# Sheet1.net
KiCad netlist of a schematic drawn in Altium Designer
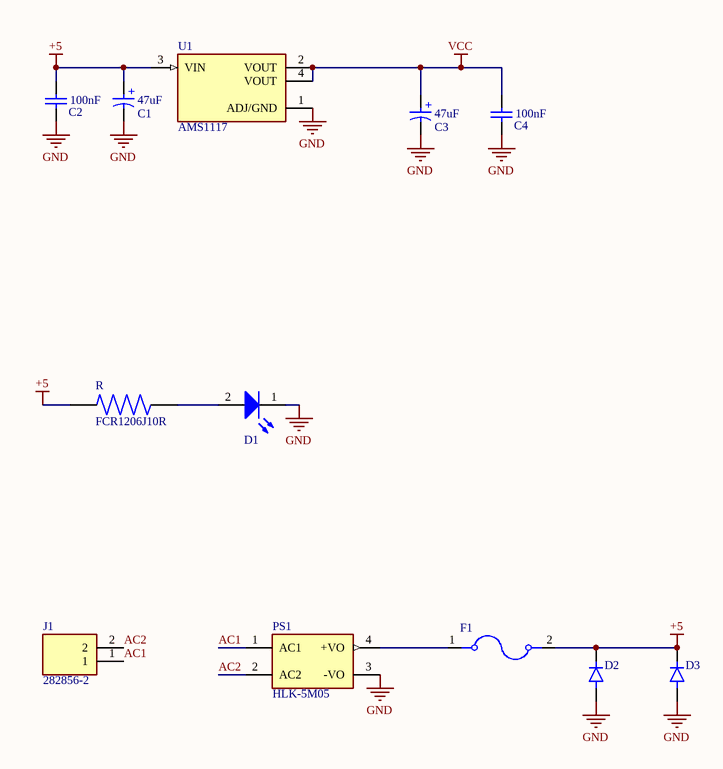
[diagram p0: Sheet1.SchDoc]

(export (version "E")
  (design (tool "Eeschema 10.0.6"))
  (components
    (comp (ref "C1")
      (value "47uF")
      (footprint "WCAP-ASLI_D6.3H7.7")
      (description "WCAP-ASLI Aluminum Electrolytic Capacitor, V-Chip, D6.3 x H5.5mm, 47uF, 25V")
      (fields
        (field (name "MANUFACTURER PART NUMBER") "865080443007")
        (field (name "MANUFACTURER") "Wurth Elektronik")
        (field (name "CAPACITANCE") "47uF")
      )
      (libsource (lib "input") (part "865080443007"))
    )
    (comp (ref "C2")
      (value "100nF")
      (footprint "WCAP-CSGP_0603_L1.6W0.8H0.8_Wave")
      (description "WCAP-CSGP Multilayer Ceramic Chip Capacitor, General Purpose, size 0603, X7R, 100nF, 25VDC")
      (fields
        (field (name "MANUFACTURER PART NUMBER") "885012206071")
        (field (name "MANUFACTURER") "Wurth Elektronik")
      )
      (libsource (lib "input") (part "885012206071"))
    )
    (comp (ref "C3")
      (value "47uF")
      (footprint "WCAP-ASLI_D6.3H7.7")
      (description "WCAP-ASLI Aluminum Electrolytic Capacitor, V-Chip, D6.3 x H5.5mm, 47uF, 25V")
      (fields
        (field (name "MANUFACTURER PART NUMBER") "865080443007")
        (field (name "MANUFACTURER") "Wurth Elektronik")
        (field (name "CAPACITANCE") "47uF")
      )
      (libsource (lib "input") (part "865080443007"))
    )
    (comp (ref "C4")
      (value "100nF")
      (footprint "WCAP-CSGP_0603_L1.6W0.8H0.8_Wave")
      (description "WCAP-CSGP Multilayer Ceramic Chip Capacitor, General Purpose, size 0603, X7R, 100nF, 25VDC")
      (fields
        (field (name "MANUFACTURER PART NUMBER") "885012206071")
        (field (name "MANUFACTURER") "Wurth Elektronik")
        (field (name "CAPACITANCE") "100nF")
      )
      (libsource (lib "input") (part "885012206071"))
    )
    (comp (ref "D1")
      (value "Infrared, 1.4V, 140°")
      (footprint "WL-SICW_1206_L3.2W1.6H1.1")
      (description "WL-SICW SMT Chip LED Infrared Waterclear, size 1206, Infrared, 1.4V, 140°")
      (fields
        (field (name "MANUFACTURER PART NUMBER") "15412085BA400")
        (field (name "MANUFACTURER") "Wurth Elektronik")
      )
      (libsource (lib "input") (part "15412085BA400"))
    )
    (comp (ref "D2")
      (value "S1G")
      (footprint "DIO_S1G")
      (description "Diode Standard 400 V 1A Surface Mount DO-214AC (SMA)")
      (fields (field (name "MF") "ON Semiconductor"))
      (libsource (lib "input") (part "S1G"))
    )
    (comp (ref "D3")
      (value "S1G")
      (footprint "DIO_S1G")
      (description "Diode Standard 400 V 1A Surface Mount DO-214AC (SMA)")
      (fields (field (name "MF") "ON Semiconductor"))
      (libsource (lib "input") (part "S1G"))
    )
    (comp (ref "F1")
      (value "0154004.DR")
      (footprint "input:FUSE_0154004.DR")
      (description "154/154T/154L/154TL Series OMNI-BLOKÂ® Fuse and Holder Assembly")
      (libsource (lib "input") (part "0154004.DR"))
    )
    (comp (ref "J1")
      (value "282856-2")
      (footprint "TE_282856-2")
      (description "TERMI-BLOK PCB MOUNT 2P")
      (fields (field (name "MF") "TE Connectivity"))
      (libsource (lib "input") (part "282856-2"))
    )
    (comp (ref "PS1")
      (value "HLK-5M05")
      (footprint "CONV_HLK-5M05")
      (description "AC DC 220V to 5V 5W 5Watt Isolated Switching Step-Down Power Supply Module Converter")
      (fields (field (name "MF") "Hi-link"))
      (libsource (lib "input") (part "HLK-5M05"))
    )
    (comp (ref "R")
      (value "FCR1206J10R")
      (footprint "RESC3216X70N")
      (description "Res 1206 10 Ohm 5% 1/8W Â±500ppm/Â°C Molded SMD SMD T/R")
      (fields (field (name "TOLERANCE") "5%") (field (name "MF") "TE Connectivity"))
      (libsource (lib "input") (part "FCR1206J10R"))
    )
    (comp (ref "U1")
      (value "AMS1117")
      (footprint "SOT229P700X180-4N")
      (description "1A LOW DROPOUT VOLTAGE REGULATOR SOT-223")
      (fields (field (name "MF") "Advanced Monolithic Systems"))
      (libsource (lib "input") (part "AMS1117"))
    )
  )
  (nets
    (net (code "1") (name "+5") (class "Default")
      (node (ref "C1") (pin "1") (pinfunction "P_1") (pintype "passive"))
      (node (ref "C2") (pin "2") (pinfunction "2_2") (pintype "passive"))
      (node (ref "D2") (pin "1") (pinfunction "K_1") (pintype "passive"))
      (node (ref "D3") (pin "1") (pinfunction "K_1") (pintype "passive"))
      (node (ref "F1") (pin "2") (pinfunction "2_2") (pintype "passive"))
      (node (ref "R") (pin "1") (pinfunction "1_1") (pintype "passive"))
      (node (ref "U1") (pin "3") (pinfunction "VIN_3") (pintype "input"))
    )
    (net (code "2") (name "/AC1") (class "Default")
      (node (ref "J1") (pin "1") (pinfunction "1_1") (pintype "passive"))
      (node (ref "PS1") (pin "1") (pinfunction "AC1_1") (pintype "power_in"))
    )
    (net (code "3") (name "/AC2") (class "Default")
      (node (ref "J1") (pin "2") (pinfunction "2_2") (pintype "passive"))
      (node (ref "PS1") (pin "2") (pinfunction "AC2_2") (pintype "power_in"))
    )
    (net (code "4") (name "GND") (class "Default")
      (node (ref "C1") (pin "2") (pinfunction "N_2") (pintype "passive"))
      (node (ref "C2") (pin "1") (pinfunction "1_1") (pintype "passive"))
      (node (ref "C3") (pin "2") (pinfunction "N_2") (pintype "passive"))
      (node (ref "C4") (pin "1") (pinfunction "1_1") (pintype "passive"))
      (node (ref "D1") (pin "1") (pinfunction "K_1") (pintype "passive"))
      (node (ref "D2") (pin "2") (pinfunction "A_2") (pintype "passive"))
      (node (ref "D3") (pin "2") (pinfunction "A_2") (pintype "passive"))
      (node (ref "PS1") (pin "3") (pinfunction "-VO_3") (pintype "power_in"))
      (node (ref "U1") (pin "1") (pinfunction "ADJ/GND_1") (pintype "power_in"))
    )
    (net (code "5") (name "Net-(D1-A)") (class "Default")
      (node (ref "D1") (pin "2") (pinfunction "A_2") (pintype "passive"))
      (node (ref "R") (pin "2") (pinfunction "2_2") (pintype "passive"))
    )
    (net (code "6") (name "Net-(PS1-+VO)") (class "Default")
      (node (ref "F1") (pin "1") (pinfunction "1_1") (pintype "passive"))
      (node (ref "PS1") (pin "4") (pinfunction "+VO_4") (pintype "output"))
    )
    (net (code "7") (name "VCC") (class "Default")
      (node (ref "C3") (pin "1") (pinfunction "P_1") (pintype "passive"))
      (node (ref "C4") (pin "2") (pinfunction "2_2") (pintype "passive"))
      (node (ref "U1") (pin "2") (pinfunction "VOUT_2") (pintype "power_in"))
      (node (ref "U1") (pin "4") (pinfunction "VOUT_4") (pintype "power_in"))
    )
  )
)
